# mrShark_Adapter.net
KiCad netlist of a schematic drawn in EAGLE
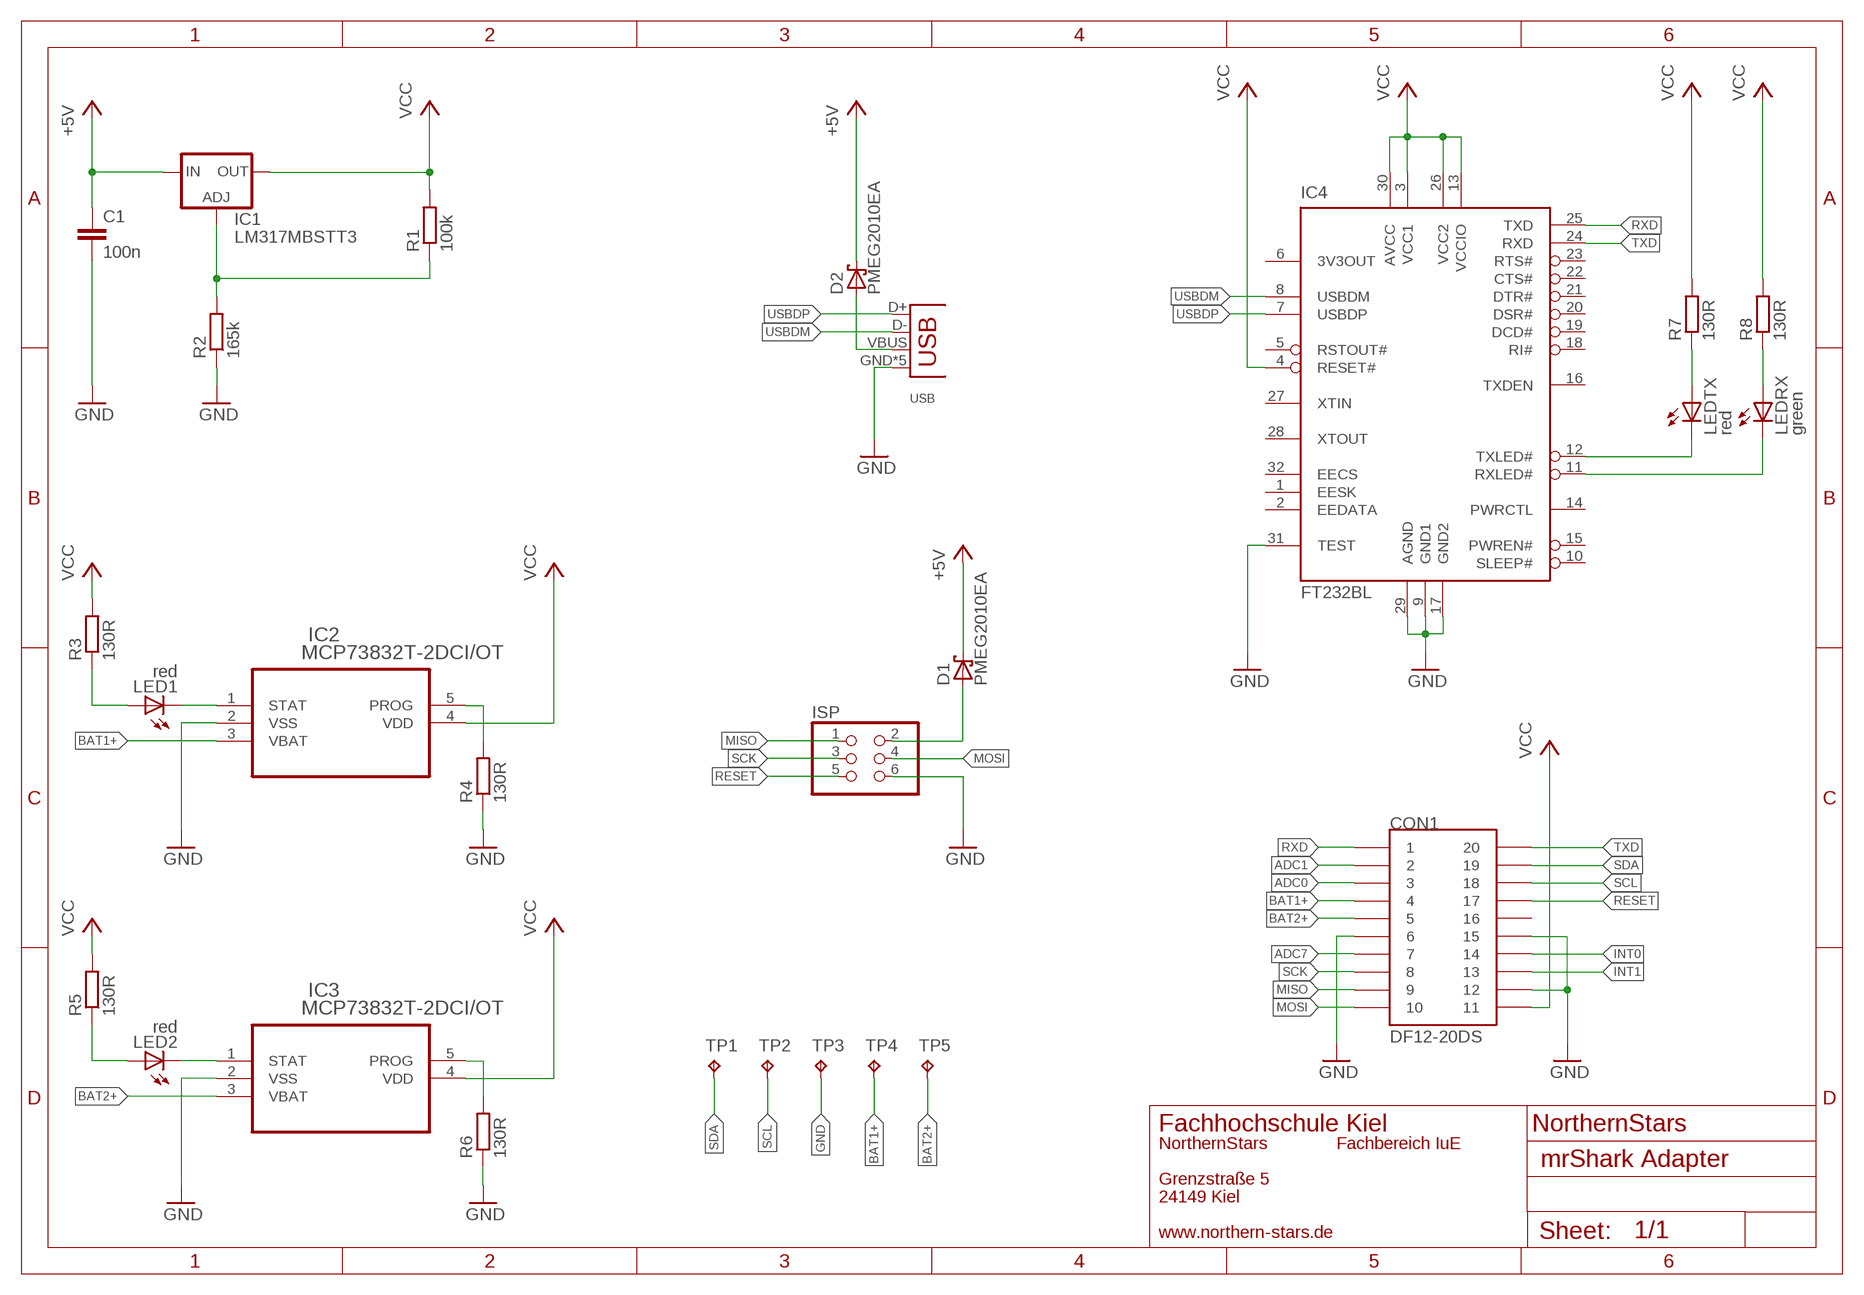
[diagram p0: schematic, sheet 1]

(export (version "E")
  (design (tool "Eeschema 10.0.6"))
  (components
    (comp (ref "C1")
      (value "100n")
      (footprint "eagle-import:C0603")
      (libsource (lib "eagle-import") (part "C-EUC0603"))
    )
    (comp (ref "CON1")
      (value "DF12-20DS")
      (footprint "eagle-import:DF12-20DS")
      (libsource (lib "eagle-import") (part "DF12-20DS"))
    )
    (comp (ref "D1")
      (value "PMEG2010EA")
      (footprint "eagle-import:SOD323-R")
      (libsource (lib "eagle-import") (part "PMEG2010EAR"))
    )
    (comp (ref "D2")
      (value "PMEG2010EA")
      (footprint "eagle-import:SOD323-R")
      (libsource (lib "eagle-import") (part "PMEG2010EAR"))
    )
    (comp (ref "IC1")
      (value "LM317MBSTT3")
      (footprint "eagle-import:SOT223")
      (libsource (lib "eagle-import") (part "LM317?MBSTT3"))
    )
    (comp (ref "IC2")
      (value "MCP73832T-2DCI/OT")
      (footprint "eagle-import:SOT95P300X145-5N")
      (libsource (lib "eagle-import") (part "MCP73832T-2DCI/OT"))
    )
    (comp (ref "IC3")
      (value "MCP73832T-2DCI/OT")
      (footprint "eagle-import:SOT95P300X145-5N")
      (libsource (lib "eagle-import") (part "MCP73832T-2DCI/OT"))
    )
    (comp (ref "IC4")
      (value "FT232BL")
      (footprint "eagle-import:LQFP32")
      (libsource (lib "eagle-import") (part "FT232BL"))
    )
    (comp (ref "ISP")
      (value "PINHD-2X03_2.54-SMD")
      (footprint "eagle-import:2X03SMD")
      (libsource (lib "eagle-import") (part "PINHD-2X03_2.54-SMD"))
    )
    (comp (ref "LED1")
      (value "red")
      (footprint "eagle-import:CHIP-LED0603")
      (libsource (lib "eagle-import") (part "LEDCHIP-LED0603"))
    )
    (comp (ref "LED2")
      (value "red")
      (footprint "eagle-import:CHIP-LED0603")
      (libsource (lib "eagle-import") (part "LEDCHIP-LED0603"))
    )
    (comp (ref "LEDRX")
      (value "green")
      (footprint "eagle-import:CHIPLED_1206")
      (libsource (lib "eagle-import") (part "LEDCHIPLED_1206"))
    )
    (comp (ref "LEDTX")
      (value "red")
      (footprint "eagle-import:CHIPLED_1206")
      (libsource (lib "eagle-import") (part "LEDCHIPLED_1206"))
    )
    (comp (ref "R1")
      (value "100k")
      (footprint "eagle-import:R0603")
      (libsource (lib "eagle-import") (part "R-EU_R0603"))
    )
    (comp (ref "R2")
      (value "165k")
      (footprint "eagle-import:R0603")
      (libsource (lib "eagle-import") (part "R-EU_R0603"))
    )
    (comp (ref "R3")
      (value "130R")
      (footprint "eagle-import:R0603")
      (libsource (lib "eagle-import") (part "R-EU_R0603"))
    )
    (comp (ref "R4")
      (value "130R")
      (footprint "eagle-import:R0603")
      (libsource (lib "eagle-import") (part "R-EU_R0603"))
    )
    (comp (ref "R5")
      (value "130R")
      (footprint "eagle-import:R0603")
      (libsource (lib "eagle-import") (part "R-EU_R0603"))
    )
    (comp (ref "R6")
      (value "130R")
      (footprint "eagle-import:R0603")
      (libsource (lib "eagle-import") (part "R-EU_R0603"))
    )
    (comp (ref "R7")
      (value "130R")
      (footprint "eagle-import:R0603")
      (libsource (lib "eagle-import") (part "R-EU_R0603"))
    )
    (comp (ref "R8")
      (value "130R")
      (footprint "eagle-import:R0603")
      (libsource (lib "eagle-import") (part "R-EU_R0603"))
    )
    (comp (ref "TP1")
      (value "TPTP06SQ")
      (footprint "eagle-import:TP06SQ")
      (libsource (lib "eagle-import") (part "TPTP06SQ"))
    )
    (comp (ref "TP2")
      (value "TPTP06SQ")
      (footprint "eagle-import:TP06SQ")
      (libsource (lib "eagle-import") (part "TPTP06SQ"))
    )
    (comp (ref "TP3")
      (value "TPTP06SQ")
      (footprint "eagle-import:TP06SQ")
      (libsource (lib "eagle-import") (part "TPTP06SQ"))
    )
    (comp (ref "TP4")
      (value "TPTP06SQ")
      (footprint "eagle-import:TP06SQ")
      (libsource (lib "eagle-import") (part "TPTP06SQ"))
    )
    (comp (ref "TP5")
      (value "TPTP06SQ")
      (footprint "eagle-import:TP06SQ")
      (libsource (lib "eagle-import") (part "TPTP06SQ"))
    )
    (comp (ref "USB")
      (value "USB-MIC-S")
      (footprint "eagle-import:USB-MIC-S")
      (libsource (lib "eagle-import") (part "USB-MIC-S"))
    )
  )
  (nets
    (net (code "1") (name "+5V") (class "Default")
      (node (ref "C1") (pin "1") (pinfunction "1_1") (pintype "passive"))
      (node (ref "D1") (pin "C") (pinfunction "C_C") (pintype "passive"))
      (node (ref "D2") (pin "C") (pinfunction "C_C") (pintype "passive"))
      (node (ref "IC1") (pin "3") (pinfunction "IN_3") (pintype "input"))
    )
    (net (code "2") (name "ADC0") (class "Default")
      (node (ref "CON1") (pin "3") (pinfunction "3_3") (pintype "bidirectional"))
    )
    (net (code "3") (name "ADC1") (class "Default")
      (node (ref "CON1") (pin "2") (pinfunction "2_2") (pintype "bidirectional"))
    )
    (net (code "4") (name "ADC7") (class "Default")
      (node (ref "CON1") (pin "7") (pinfunction "7_7") (pintype "bidirectional"))
    )
    (net (code "5") (name "BAT1+") (class "Default")
      (node (ref "CON1") (pin "4") (pinfunction "4_4") (pintype "bidirectional"))
      (node (ref "IC2") (pin "3") (pinfunction "VBAT_3") (pintype "input"))
      (node (ref "TP4") (pin "TP") (pinfunction "TP_TP") (pintype "input"))
    )
    (net (code "6") (name "BAT2+") (class "Default")
      (node (ref "CON1") (pin "5") (pinfunction "5_5") (pintype "bidirectional"))
      (node (ref "IC3") (pin "3") (pinfunction "VBAT_3") (pintype "input"))
      (node (ref "TP5") (pin "TP") (pinfunction "TP_TP") (pintype "input"))
    )
    (net (code "7") (name "GND") (class "Default")
      (node (ref "C1") (pin "2") (pinfunction "2_2") (pintype "passive"))
      (node (ref "CON1") (pin "12") (pinfunction "12_12") (pintype "bidirectional"))
      (node (ref "CON1") (pin "15") (pinfunction "15_15") (pintype "bidirectional"))
      (node (ref "CON1") (pin "6") (pinfunction "6_6") (pintype "bidirectional"))
      (node (ref "IC2") (pin "2") (pinfunction "VSS_2") (pintype "passive"))
      (node (ref "IC3") (pin "2") (pinfunction "VSS_2") (pintype "passive"))
      (node (ref "IC4") (pin "17") (pinfunction "GND2_17") (pintype "power_in"))
      (node (ref "IC4") (pin "29") (pinfunction "AGND_29") (pintype "power_in"))
      (node (ref "IC4") (pin "31") (pinfunction "TEST_31") (pintype "input"))
      (node (ref "IC4") (pin "9") (pinfunction "GND1_9") (pintype "power_in"))
      (node (ref "ISP") (pin "6") (pinfunction "6_6") (pintype "passive"))
      (node (ref "R2") (pin "1") (pinfunction "1_1") (pintype "passive"))
      (node (ref "R4") (pin "1") (pinfunction "1_1") (pintype "passive"))
      (node (ref "R6") (pin "1") (pinfunction "1_1") (pintype "passive"))
      (node (ref "TP3") (pin "TP") (pinfunction "TP_TP") (pintype "input"))
      (node (ref "USB") (pin "GND") (pinfunction "GND_GND") (pintype "bidirectional"))
      (node (ref "USB") (pin "P$11") (pinfunction "GND_P$11") (pintype "bidirectional"))
      (node (ref "USB") (pin "P$12") (pinfunction "GND_P$12") (pintype "bidirectional"))
      (node (ref "USB") (pin "P$13") (pinfunction "GND_P$13") (pintype "bidirectional"))
      (node (ref "USB") (pin "P$14") (pinfunction "GND_P$14") (pintype "bidirectional"))
    )
    (net (code "8") (name "INT0") (class "Default")
      (node (ref "CON1") (pin "14") (pinfunction "14_14") (pintype "bidirectional"))
    )
    (net (code "9") (name "INT1") (class "Default")
      (node (ref "CON1") (pin "13") (pinfunction "13_13") (pintype "bidirectional"))
    )
    (net (code "10") (name "MISO") (class "Default")
      (node (ref "CON1") (pin "9") (pinfunction "9_9") (pintype "bidirectional"))
      (node (ref "ISP") (pin "1") (pinfunction "1_1") (pintype "passive"))
    )
    (net (code "11") (name "MOSI") (class "Default")
      (node (ref "CON1") (pin "10") (pinfunction "10_10") (pintype "bidirectional"))
      (node (ref "ISP") (pin "4") (pinfunction "4_4") (pintype "passive"))
    )
    (net (code "12") (name "Net-(D1-PadA)") (class "Default")
      (node (ref "D1") (pin "A") (pinfunction "A_A") (pintype "passive"))
      (node (ref "ISP") (pin "2") (pinfunction "2_2") (pintype "passive"))
    )
    (net (code "13") (name "Net-(D2-PadA)") (class "Default")
      (node (ref "D2") (pin "A") (pinfunction "A_A") (pintype "passive"))
      (node (ref "USB") (pin "VBUS") (pinfunction "VBUS_VBUS") (pintype "bidirectional"))
    )
    (net (code "14") (name "Net-(IC1-ADJ)") (class "Default")
      (node (ref "IC1") (pin "1") (pinfunction "ADJ_1") (pintype "input"))
      (node (ref "R1") (pin "1") (pinfunction "1_1") (pintype "passive"))
      (node (ref "R2") (pin "2") (pinfunction "2_2") (pintype "passive"))
    )
    (net (code "15") (name "Net-(IC2-PROG)") (class "Default")
      (node (ref "IC2") (pin "5") (pinfunction "PROG_5") (pintype "input"))
      (node (ref "R4") (pin "2") (pinfunction "2_2") (pintype "passive"))
    )
    (net (code "16") (name "Net-(IC2-STAT)") (class "Default")
      (node (ref "IC2") (pin "1") (pinfunction "STAT_1") (pintype "input"))
      (node (ref "LED1") (pin "C") (pinfunction "C_C") (pintype "passive"))
    )
    (net (code "17") (name "Net-(IC3-PROG)") (class "Default")
      (node (ref "IC3") (pin "5") (pinfunction "PROG_5") (pintype "input"))
      (node (ref "R6") (pin "2") (pinfunction "2_2") (pintype "passive"))
    )
    (net (code "18") (name "Net-(IC3-STAT)") (class "Default")
      (node (ref "IC3") (pin "1") (pinfunction "STAT_1") (pintype "input"))
      (node (ref "LED2") (pin "C") (pinfunction "C_C") (pintype "passive"))
    )
    (net (code "19") (name "Net-(IC4-RXLED#)") (class "Default")
      (node (ref "IC4") (pin "11") (pinfunction "RXLED#_11") (pintype "open_collector"))
      (node (ref "LEDRX") (pin "C") (pinfunction "C_C") (pintype "passive"))
    )
    (net (code "20") (name "Net-(IC4-TXLED#)") (class "Default")
      (node (ref "IC4") (pin "12") (pinfunction "TXLED#_12") (pintype "open_collector"))
      (node (ref "LEDTX") (pin "C") (pinfunction "C_C") (pintype "passive"))
    )
    (net (code "21") (name "Net-(LED1-PadA)") (class "Default")
      (node (ref "LED1") (pin "A") (pinfunction "A_A") (pintype "passive"))
      (node (ref "R3") (pin "1") (pinfunction "1_1") (pintype "passive"))
    )
    (net (code "22") (name "Net-(LED2-PadA)") (class "Default")
      (node (ref "LED2") (pin "A") (pinfunction "A_A") (pintype "passive"))
      (node (ref "R5") (pin "1") (pinfunction "1_1") (pintype "passive"))
    )
    (net (code "23") (name "Net-(LEDRX-PadA)") (class "Default")
      (node (ref "LEDRX") (pin "A") (pinfunction "A_A") (pintype "passive"))
      (node (ref "R8") (pin "1") (pinfunction "1_1") (pintype "passive"))
    )
    (net (code "24") (name "Net-(LEDTX-PadA)") (class "Default")
      (node (ref "LEDTX") (pin "A") (pinfunction "A_A") (pintype "passive"))
      (node (ref "R7") (pin "1") (pinfunction "1_1") (pintype "passive"))
    )
    (net (code "25") (name "RESET") (class "Default")
      (node (ref "CON1") (pin "17") (pinfunction "17_17") (pintype "bidirectional"))
      (node (ref "ISP") (pin "5") (pinfunction "5_5") (pintype "passive"))
    )
    (net (code "26") (name "RXD") (class "Default")
      (node (ref "CON1") (pin "1") (pinfunction "1_1") (pintype "bidirectional"))
      (node (ref "IC4") (pin "25") (pinfunction "TXD_25") (pintype "output"))
    )
    (net (code "27") (name "SCK") (class "Default")
      (node (ref "CON1") (pin "8") (pinfunction "8_8") (pintype "bidirectional"))
      (node (ref "ISP") (pin "3") (pinfunction "3_3") (pintype "passive"))
    )
    (net (code "28") (name "SCL") (class "Default")
      (node (ref "CON1") (pin "18") (pinfunction "18_18") (pintype "bidirectional"))
      (node (ref "TP2") (pin "TP") (pinfunction "TP_TP") (pintype "input"))
    )
    (net (code "29") (name "SDA") (class "Default")
      (node (ref "CON1") (pin "19") (pinfunction "19_19") (pintype "bidirectional"))
      (node (ref "TP1") (pin "TP") (pinfunction "TP_TP") (pintype "input"))
    )
    (net (code "30") (name "TXD") (class "Default")
      (node (ref "CON1") (pin "20") (pinfunction "20_20") (pintype "bidirectional"))
      (node (ref "IC4") (pin "24") (pinfunction "RXD_24") (pintype "input"))
    )
    (net (code "31") (name "USBDM") (class "Default")
      (node (ref "IC4") (pin "8") (pinfunction "USBDM_8") (pintype "bidirectional"))
      (node (ref "USB") (pin "D-") (pinfunction "D-_D-") (pintype "bidirectional"))
    )
    (net (code "32") (name "USBDP") (class "Default")
      (node (ref "IC4") (pin "7") (pinfunction "USBDP_7") (pintype "bidirectional"))
      (node (ref "USB") (pin "D+") (pinfunction "D+_D+") (pintype "bidirectional"))
    )
    (net (code "33") (name "VCC") (class "Default")
      (node (ref "CON1") (pin "11") (pinfunction "11_11") (pintype "bidirectional"))
      (node (ref "IC1") (pin "4") (pinfunction "OUT_4") (pintype "passive"))
      (node (ref "IC2") (pin "4") (pinfunction "VDD_4") (pintype "power_in"))
      (node (ref "IC3") (pin "4") (pinfunction "VDD_4") (pintype "power_in"))
      (node (ref "IC4") (pin "13") (pinfunction "VCCIO_13") (pintype "power_in"))
      (node (ref "IC4") (pin "26") (pinfunction "VCC2_26") (pintype "power_in"))
      (node (ref "IC4") (pin "3") (pinfunction "VCC1_3") (pintype "power_in"))
      (node (ref "IC4") (pin "30") (pinfunction "AVCC_30") (pintype "power_in"))
      (node (ref "IC4") (pin "4") (pinfunction "RESET#_4") (pintype "input"))
      (node (ref "R1") (pin "2") (pinfunction "2_2") (pintype "passive"))
      (node (ref "R3") (pin "2") (pinfunction "2_2") (pintype "passive"))
      (node (ref "R5") (pin "2") (pinfunction "2_2") (pintype "passive"))
      (node (ref "R7") (pin "2") (pinfunction "2_2") (pintype "passive"))
      (node (ref "R8") (pin "2") (pinfunction "2_2") (pintype "passive"))
    )
    (net (code "34") (name "unconnected-(CON1-Pad16)") (class "Default")
      (node (ref "CON1") (pin "16") (pinfunction "16_16") (pintype "bidirectional"))
    )
    (net (code "35") (name "unconnected-(IC4-3V3OUT-Pad6)") (class "Default")
      (node (ref "IC4") (pin "6") (pinfunction "3V3OUT_6") (pintype "output"))
    )
    (net (code "36") (name "unconnected-(IC4-CTS#-Pad22)") (class "Default")
      (node (ref "IC4") (pin "22") (pinfunction "CTS#_22") (pintype "input"))
    )
    (net (code "37") (name "unconnected-(IC4-DCD#-Pad19)") (class "Default")
      (node (ref "IC4") (pin "19") (pinfunction "DCD#_19") (pintype "input"))
    )
    (net (code "38") (name "unconnected-(IC4-DSR#-Pad20)") (class "Default")
      (node (ref "IC4") (pin "20") (pinfunction "DSR#_20") (pintype "input"))
    )
    (net (code "39") (name "unconnected-(IC4-DTR#-Pad21)") (class "Default")
      (node (ref "IC4") (pin "21") (pinfunction "DTR#_21") (pintype "output"))
    )
    (net (code "40") (name "unconnected-(IC4-EECS-Pad32)") (class "Default")
      (node (ref "IC4") (pin "32") (pinfunction "EECS_32") (pintype "bidirectional"))
    )
    (net (code "41") (name "unconnected-(IC4-EEDATA-Pad2)") (class "Default")
      (node (ref "IC4") (pin "2") (pinfunction "EEDATA_2") (pintype "bidirectional"))
    )
    (net (code "42") (name "unconnected-(IC4-EESK-Pad1)") (class "Default")
      (node (ref "IC4") (pin "1") (pinfunction "EESK_1") (pintype "output"))
    )
    (net (code "43") (name "unconnected-(IC4-PWRCTL-Pad14)") (class "Default")
      (node (ref "IC4") (pin "14") (pinfunction "PWRCTL_14") (pintype "input"))
    )
    (net (code "44") (name "unconnected-(IC4-PWREN#-Pad15)") (class "Default")
      (node (ref "IC4") (pin "15") (pinfunction "PWREN#_15") (pintype "output"))
    )
    (net (code "45") (name "unconnected-(IC4-RI#-Pad18)") (class "Default")
      (node (ref "IC4") (pin "18") (pinfunction "RI#_18") (pintype "input"))
    )
    (net (code "46") (name "unconnected-(IC4-RSTOUT#-Pad5)") (class "Default")
      (node (ref "IC4") (pin "5") (pinfunction "RSTOUT#_5") (pintype "output"))
    )
    (net (code "47") (name "unconnected-(IC4-RTS#-Pad23)") (class "Default")
      (node (ref "IC4") (pin "23") (pinfunction "RTS#_23") (pintype "output"))
    )
    (net (code "48") (name "unconnected-(IC4-SLEEP#-Pad10)") (class "Default")
      (node (ref "IC4") (pin "10") (pinfunction "SLEEP#_10") (pintype "output"))
    )
    (net (code "49") (name "unconnected-(IC4-TXDEN-Pad16)") (class "Default")
      (node (ref "IC4") (pin "16") (pinfunction "TXDEN_16") (pintype "output"))
    )
    (net (code "50") (name "unconnected-(IC4-XTIN-Pad27)") (class "Default")
      (node (ref "IC4") (pin "27") (pinfunction "XTIN_27") (pintype "input"))
    )
    (net (code "51") (name "unconnected-(IC4-XTOUT-Pad28)") (class "Default")
      (node (ref "IC4") (pin "28") (pinfunction "XTOUT_28") (pintype "output"))
    )
  )
)
